# Addon-mapleCUx_Raspi-3V3-UART-CC2530-V04.net
KiCad netlist of a schematic drawn in EAGLE
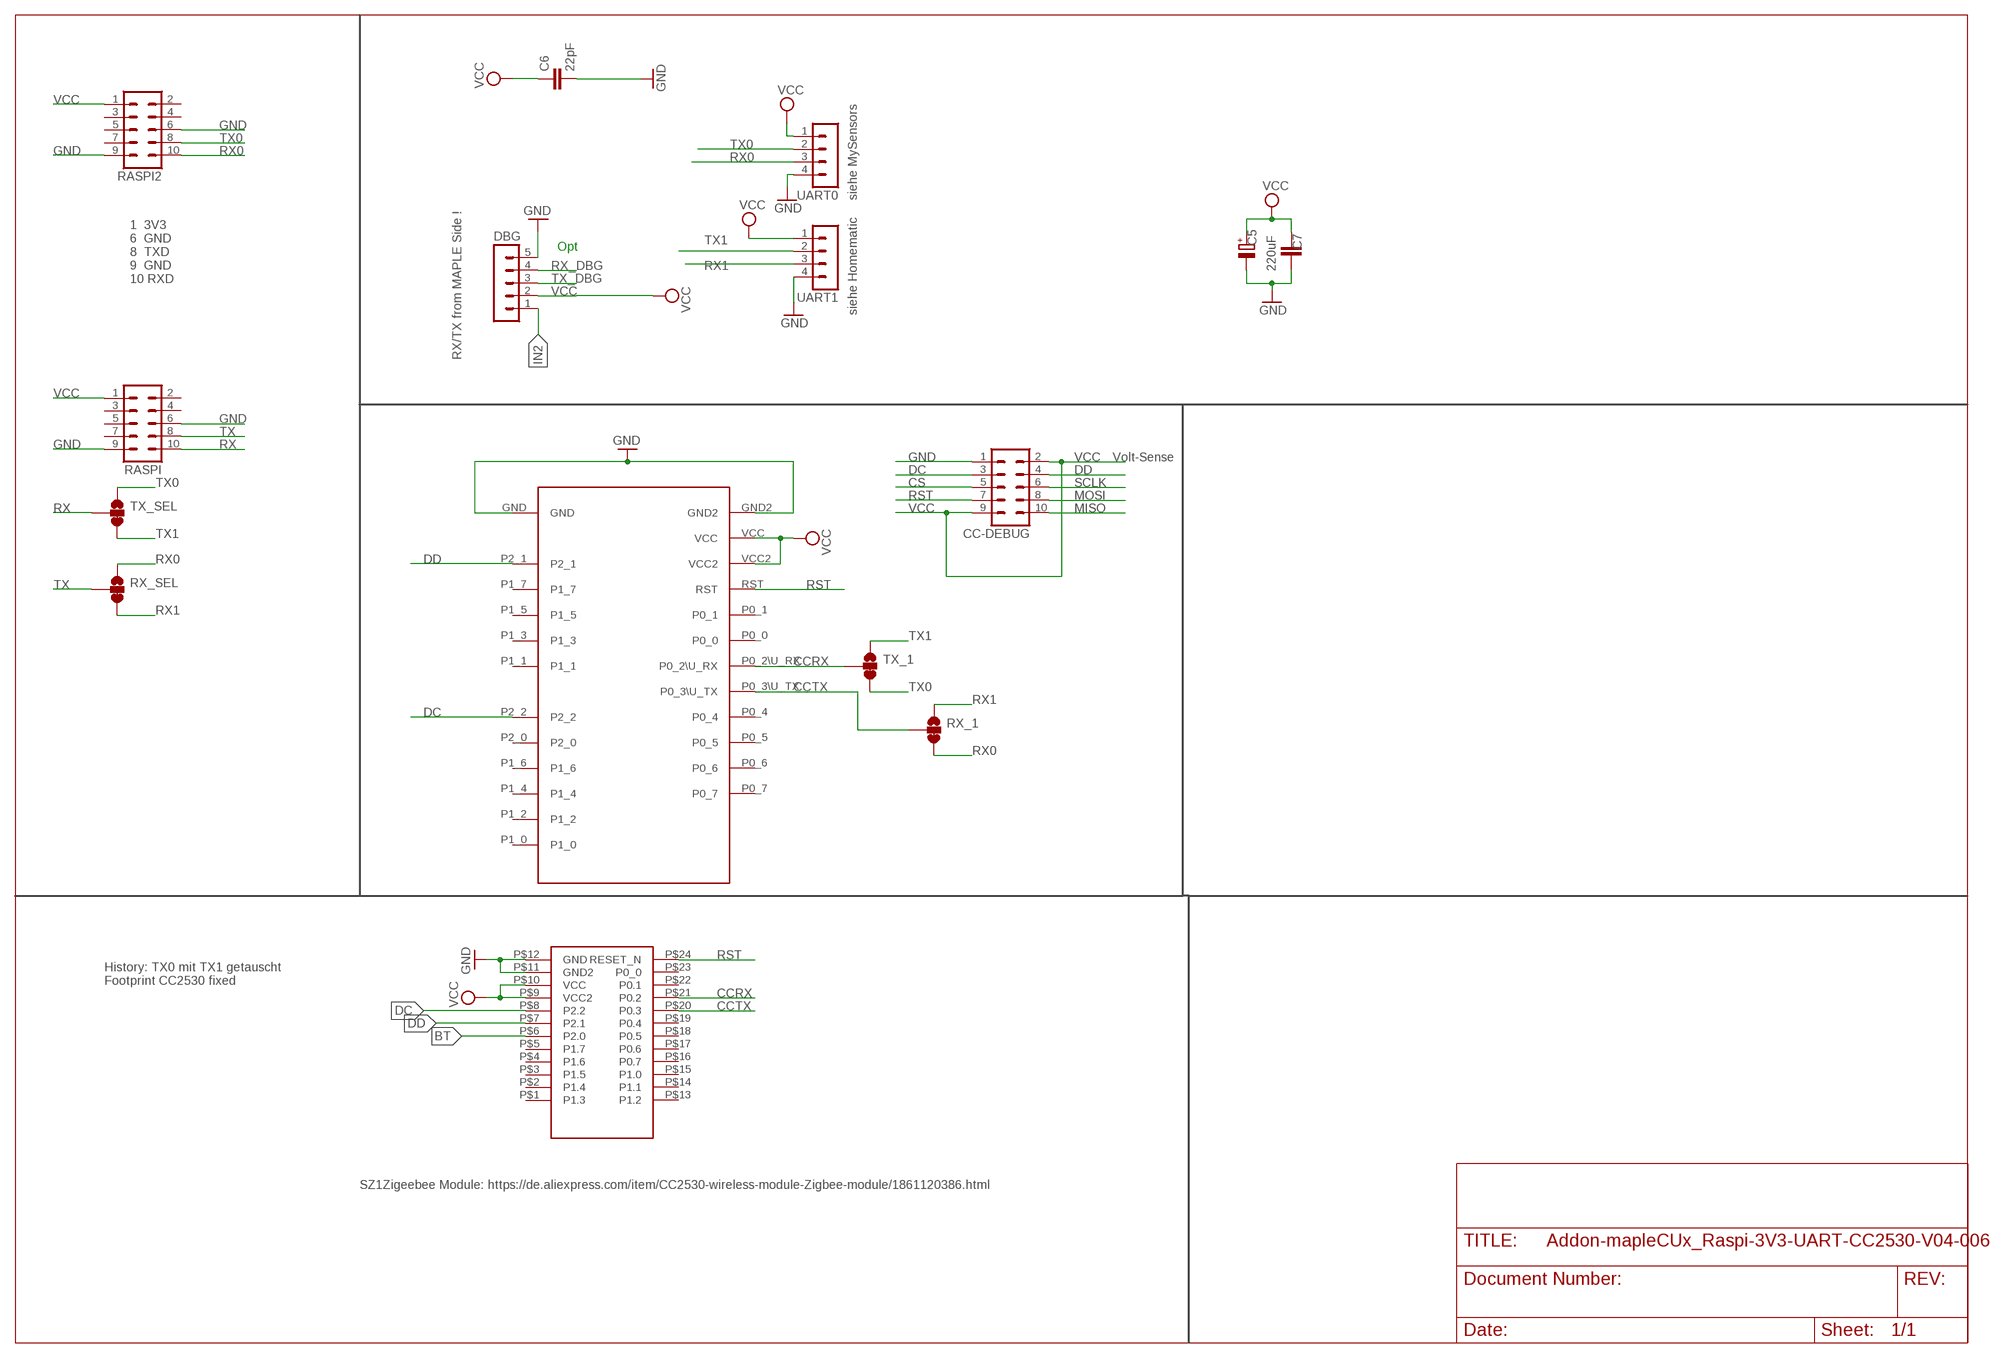
[diagram p0: schematic, sheet 1]

(export (version "E")
  (design (tool "Eeschema 10.0.6"))
  (components
    (comp (ref "C5")
      (value "220uF")
      (footprint "eagle-import:E5-8,5")
      (libsource (lib "eagle-import") (part "CPOL-EUE5-8.5"))
    )
    (comp (ref "C6")
      (value "22pF")
      (footprint "eagle-import:C0805")
      (libsource (lib "eagle-import") (part "C-EUC0805"))
    )
    (comp (ref "C7")
      (value "C-EUC1812")
      (footprint "eagle-import:C1812")
      (libsource (lib "eagle-import") (part "C-EUC1812"))
    )
    (comp (ref "CC-DEBUG")
      (value "MA05-2")
      (footprint "eagle-import:MA05-2")
      (libsource (lib "eagle-import") (part "MA05-2"))
    )
    (comp (ref "DBG")
      (value "MA05-1")
      (footprint "eagle-import:MA05-1")
      (libsource (lib "eagle-import") (part "MA05-1"))
    )
    (comp (ref "RASPI")
      (value "MA05-2")
      (footprint "eagle-import:MA05-2")
      (libsource (lib "eagle-import") (part "MA05-2"))
    )
    (comp (ref "RASPI2")
      (value "MA05-2")
      (footprint "eagle-import:MA05-2")
      (libsource (lib "eagle-import") (part "MA05-2"))
    )
    (comp (ref "RX_1")
      (value "JUMPER-SMT_3_1-NC_TRACE_SILK")
      (footprint "eagle-import:SMT-JUMPER_3_1-NC_TRACE_SILK")
      (libsource (lib "eagle-import") (part "JUMPER-SMT_3_1-NC_TRACE_SILK"))
    )
    (comp (ref "RX_SEL")
      (value "JUMPER-SMT_3_1-NC_TRACE_SILK")
      (footprint "eagle-import:SMT-JUMPER_3_1-NC_TRACE_SILK")
      (libsource (lib "eagle-import") (part "JUMPER-SMT_3_1-NC_TRACE_SILK"))
    )
    (comp (ref "TX_1")
      (value "JUMPER-SMT_3_1-NC_TRACE_SILK")
      (footprint "eagle-import:SMT-JUMPER_3_1-NC_TRACE_SILK")
      (libsource (lib "eagle-import") (part "JUMPER-SMT_3_1-NC_TRACE_SILK"))
    )
    (comp (ref "TX_SEL")
      (value "JUMPER-SMT_3_1-NC_TRACE_SILK")
      (footprint "eagle-import:SMT-JUMPER_3_1-NC_TRACE_SILK")
      (libsource (lib "eagle-import") (part "JUMPER-SMT_3_1-NC_TRACE_SILK"))
    )
    (comp (ref "U$1")
      (value "CC2530CC2530PA")
      (footprint "eagle-import:CC2530PA")
      (libsource (lib "eagle-import") (part "CC2530CC2530PA"))
    )
    (comp (ref "U$3")
      (value "CC2530_MODULE")
      (footprint "eagle-import:CC2530_DIL")
      (libsource (lib "eagle-import") (part "CC2530_MODULE"))
    )
    (comp (ref "UART0")
      (value "MA04-1")
      (footprint "eagle-import:MA04-1")
      (libsource (lib "eagle-import") (part "MA04-1"))
    )
    (comp (ref "UART1")
      (value "MA04-1")
      (footprint "eagle-import:MA04-1")
      (libsource (lib "eagle-import") (part "MA04-1"))
    )
  )
  (nets
    (net (code "1") (name "/CCRX") (class "Default")
      (node (ref "TX_1") (pin "2") (pinfunction "2_2") (pintype "passive"))
      (node (ref "U$1") (pin "P$21") (pinfunction "P0.2_P$21") (pintype "bidirectional"))
      (node (ref "U$3") (pin "P0_2\\U_RX") (pinfunction "P0_2\\U_RX_P0_2\\U_RX") (pintype "bidirectional"))
    )
    (net (code "2") (name "/CCTX") (class "Default")
      (node (ref "RX_1") (pin "2") (pinfunction "2_2") (pintype "passive"))
      (node (ref "U$1") (pin "P$20") (pinfunction "P0.3_P$20") (pintype "bidirectional"))
      (node (ref "U$3") (pin "P0_3\\U_TX") (pinfunction "P0_3\\U_TX_P0_3\\U_TX") (pintype "bidirectional"))
    )
    (net (code "3") (name "/CS") (class "Default")
      (node (ref "CC-DEBUG") (pin "5") (pinfunction "5_5") (pintype "passive"))
    )
    (net (code "4") (name "/MISO") (class "Default")
      (node (ref "CC-DEBUG") (pin "10") (pinfunction "10_10") (pintype "passive"))
    )
    (net (code "5") (name "/MOSI") (class "Default")
      (node (ref "CC-DEBUG") (pin "8") (pinfunction "8_8") (pintype "passive"))
    )
    (net (code "6") (name "/RST") (class "Default")
      (node (ref "CC-DEBUG") (pin "7") (pinfunction "7_7") (pintype "passive"))
      (node (ref "U$1") (pin "P$24") (pinfunction "RESET_N_P$24") (pintype "bidirectional"))
      (node (ref "U$3") (pin "RST") (pinfunction "RST_RST") (pintype "bidirectional"))
    )
    (net (code "7") (name "/RX") (class "Default")
      (node (ref "RASPI") (pin "10") (pinfunction "10_10") (pintype "passive"))
      (node (ref "TX_SEL") (pin "2") (pinfunction "2_2") (pintype "passive"))
    )
    (net (code "8") (name "/RX0") (class "Default")
      (node (ref "RASPI2") (pin "10") (pinfunction "10_10") (pintype "passive"))
      (node (ref "RX_1") (pin "3") (pinfunction "3_3") (pintype "passive"))
      (node (ref "RX_SEL") (pin "1") (pinfunction "1_1") (pintype "passive"))
      (node (ref "UART0") (pin "3") (pinfunction "3_3") (pintype "passive"))
    )
    (net (code "9") (name "/RX1") (class "Default")
      (node (ref "RX_1") (pin "1") (pinfunction "1_1") (pintype "passive"))
      (node (ref "RX_SEL") (pin "3") (pinfunction "3_3") (pintype "passive"))
      (node (ref "UART1") (pin "3") (pinfunction "3_3") (pintype "passive"))
    )
    (net (code "10") (name "/RX_DBG") (class "Default")
      (node (ref "DBG") (pin "4") (pinfunction "4_4") (pintype "passive"))
    )
    (net (code "11") (name "/SCLK") (class "Default")
      (node (ref "CC-DEBUG") (pin "6") (pinfunction "6_6") (pintype "passive"))
    )
    (net (code "12") (name "/TX") (class "Default")
      (node (ref "RASPI") (pin "8") (pinfunction "8_8") (pintype "passive"))
      (node (ref "RX_SEL") (pin "2") (pinfunction "2_2") (pintype "passive"))
    )
    (net (code "13") (name "/TX0") (class "Default")
      (node (ref "RASPI2") (pin "8") (pinfunction "8_8") (pintype "passive"))
      (node (ref "TX_1") (pin "3") (pinfunction "3_3") (pintype "passive"))
      (node (ref "TX_SEL") (pin "1") (pinfunction "1_1") (pintype "passive"))
      (node (ref "UART0") (pin "2") (pinfunction "2_2") (pintype "passive"))
    )
    (net (code "14") (name "/TX1") (class "Default")
      (node (ref "TX_1") (pin "1") (pinfunction "1_1") (pintype "passive"))
      (node (ref "TX_SEL") (pin "3") (pinfunction "3_3") (pintype "passive"))
      (node (ref "UART1") (pin "2") (pinfunction "2_2") (pintype "passive"))
    )
    (net (code "15") (name "/TX_DBG") (class "Default")
      (node (ref "DBG") (pin "3") (pinfunction "3_3") (pintype "passive"))
    )
    (net (code "16") (name "BT") (class "Default")
      (node (ref "U$1") (pin "P$6") (pinfunction "P2.0_P$6") (pintype "bidirectional"))
    )
    (net (code "17") (name "DC") (class "Default")
      (node (ref "CC-DEBUG") (pin "3") (pinfunction "3_3") (pintype "passive"))
      (node (ref "U$1") (pin "P$8") (pinfunction "P2.2_P$8") (pintype "bidirectional"))
      (node (ref "U$3") (pin "P2_2") (pinfunction "P2_2_P2_2") (pintype "bidirectional"))
    )
    (net (code "18") (name "DD") (class "Default")
      (node (ref "CC-DEBUG") (pin "4") (pinfunction "4_4") (pintype "passive"))
      (node (ref "U$1") (pin "P$7") (pinfunction "P2.1_P$7") (pintype "bidirectional"))
      (node (ref "U$3") (pin "P2_1") (pinfunction "P2_1_P2_1") (pintype "bidirectional"))
    )
    (net (code "19") (name "GND") (class "Default")
      (node (ref "C5") (pin "-") (pinfunction "-_-") (pintype "passive"))
      (node (ref "C6") (pin "2") (pinfunction "2_2") (pintype "passive"))
      (node (ref "C7") (pin "1") (pinfunction "1_1") (pintype "passive"))
      (node (ref "CC-DEBUG") (pin "1") (pinfunction "1_1") (pintype "passive"))
      (node (ref "DBG") (pin "5") (pinfunction "5_5") (pintype "passive"))
      (node (ref "RASPI") (pin "6") (pinfunction "6_6") (pintype "passive"))
      (node (ref "RASPI") (pin "9") (pinfunction "9_9") (pintype "passive"))
      (node (ref "RASPI2") (pin "6") (pinfunction "6_6") (pintype "passive"))
      (node (ref "RASPI2") (pin "9") (pinfunction "9_9") (pintype "passive"))
      (node (ref "U$1") (pin "P$11") (pinfunction "GND2_P$11") (pintype "bidirectional"))
      (node (ref "U$1") (pin "P$12") (pinfunction "GND_P$12") (pintype "bidirectional"))
      (node (ref "U$3") (pin "GND") (pinfunction "GND_GND") (pintype "bidirectional"))
      (node (ref "U$3") (pin "GND2") (pinfunction "GND2_GND2") (pintype "bidirectional"))
      (node (ref "UART0") (pin "4") (pinfunction "4_4") (pintype "passive"))
      (node (ref "UART1") (pin "4") (pinfunction "4_4") (pintype "passive"))
    )
    (net (code "20") (name "IN2") (class "Default")
      (node (ref "DBG") (pin "1") (pinfunction "1_1") (pintype "passive"))
    )
    (net (code "21") (name "VCC") (class "Default")
      (node (ref "C5") (pin "+") (pinfunction "+_+") (pintype "passive"))
      (node (ref "C6") (pin "1") (pinfunction "1_1") (pintype "passive"))
      (node (ref "C7") (pin "2") (pinfunction "2_2") (pintype "passive"))
      (node (ref "CC-DEBUG") (pin "2") (pinfunction "2_2") (pintype "passive"))
      (node (ref "CC-DEBUG") (pin "9") (pinfunction "9_9") (pintype "passive"))
      (node (ref "DBG") (pin "2") (pinfunction "2_2") (pintype "passive"))
      (node (ref "RASPI") (pin "1") (pinfunction "1_1") (pintype "passive"))
      (node (ref "RASPI2") (pin "1") (pinfunction "1_1") (pintype "passive"))
      (node (ref "U$1") (pin "P$10") (pinfunction "VCC_P$10") (pintype "bidirectional"))
      (node (ref "U$1") (pin "P$9") (pinfunction "VCC2_P$9") (pintype "bidirectional"))
      (node (ref "U$3") (pin "VCC") (pinfunction "VCC_VCC") (pintype "bidirectional"))
      (node (ref "U$3") (pin "VCC2") (pinfunction "VCC2_VCC2") (pintype "bidirectional"))
      (node (ref "UART0") (pin "1") (pinfunction "1_1") (pintype "passive"))
      (node (ref "UART1") (pin "1") (pinfunction "1_1") (pintype "passive"))
    )
    (net (code "22") (name "unconnected-(RASPI-Pad2)") (class "Default")
      (node (ref "RASPI") (pin "2") (pinfunction "2_2") (pintype "passive"))
    )
    (net (code "23") (name "unconnected-(RASPI-Pad3)") (class "Default")
      (node (ref "RASPI") (pin "3") (pinfunction "3_3") (pintype "passive"))
    )
    (net (code "24") (name "unconnected-(RASPI-Pad4)") (class "Default")
      (node (ref "RASPI") (pin "4") (pinfunction "4_4") (pintype "passive"))
    )
    (net (code "25") (name "unconnected-(RASPI-Pad5)") (class "Default")
      (node (ref "RASPI") (pin "5") (pinfunction "5_5") (pintype "passive"))
    )
    (net (code "26") (name "unconnected-(RASPI-Pad7)") (class "Default")
      (node (ref "RASPI") (pin "7") (pinfunction "7_7") (pintype "passive"))
    )
    (net (code "27") (name "unconnected-(RASPI2-Pad2)") (class "Default")
      (node (ref "RASPI2") (pin "2") (pinfunction "2_2") (pintype "passive"))
    )
    (net (code "28") (name "unconnected-(RASPI2-Pad3)") (class "Default")
      (node (ref "RASPI2") (pin "3") (pinfunction "3_3") (pintype "passive"))
    )
    (net (code "29") (name "unconnected-(RASPI2-Pad4)") (class "Default")
      (node (ref "RASPI2") (pin "4") (pinfunction "4_4") (pintype "passive"))
    )
    (net (code "30") (name "unconnected-(RASPI2-Pad5)") (class "Default")
      (node (ref "RASPI2") (pin "5") (pinfunction "5_5") (pintype "passive"))
    )
    (net (code "31") (name "unconnected-(RASPI2-Pad7)") (class "Default")
      (node (ref "RASPI2") (pin "7") (pinfunction "7_7") (pintype "passive"))
    )
    (net (code "32") (name "unconnected-(U$1-P0.1-PadP$22)") (class "Default")
      (node (ref "U$1") (pin "P$22") (pinfunction "P0.1_P$22") (pintype "bidirectional"))
    )
    (net (code "33") (name "unconnected-(U$1-P0.4-PadP$19)") (class "Default")
      (node (ref "U$1") (pin "P$19") (pinfunction "P0.4_P$19") (pintype "bidirectional"))
    )
    (net (code "34") (name "unconnected-(U$1-P0.5-PadP$18)") (class "Default")
      (node (ref "U$1") (pin "P$18") (pinfunction "P0.5_P$18") (pintype "bidirectional"))
    )
    (net (code "35") (name "unconnected-(U$1-P0.6-PadP$17)") (class "Default")
      (node (ref "U$1") (pin "P$17") (pinfunction "P0.6_P$17") (pintype "bidirectional"))
    )
    (net (code "36") (name "unconnected-(U$1-P0.7-PadP$16)") (class "Default")
      (node (ref "U$1") (pin "P$16") (pinfunction "P0.7_P$16") (pintype "bidirectional"))
    )
    (net (code "37") (name "unconnected-(U$1-P0_0-PadP$23)") (class "Default")
      (node (ref "U$1") (pin "P$23") (pinfunction "P0_0_P$23") (pintype "bidirectional"))
    )
    (net (code "38") (name "unconnected-(U$1-P1.0-PadP$15)") (class "Default")
      (node (ref "U$1") (pin "P$15") (pinfunction "P1.0_P$15") (pintype "bidirectional"))
    )
    (net (code "39") (name "unconnected-(U$1-P1.1-PadP$14)") (class "Default")
      (node (ref "U$1") (pin "P$14") (pinfunction "P1.1_P$14") (pintype "bidirectional"))
    )
    (net (code "40") (name "unconnected-(U$1-P1.2-PadP$13)") (class "Default")
      (node (ref "U$1") (pin "P$13") (pinfunction "P1.2_P$13") (pintype "bidirectional"))
    )
    (net (code "41") (name "unconnected-(U$1-P1.3-PadP$1)") (class "Default")
      (node (ref "U$1") (pin "P$1") (pinfunction "P1.3_P$1") (pintype "bidirectional"))
    )
    (net (code "42") (name "unconnected-(U$1-P1.4-PadP$2)") (class "Default")
      (node (ref "U$1") (pin "P$2") (pinfunction "P1.4_P$2") (pintype "bidirectional"))
    )
    (net (code "43") (name "unconnected-(U$1-P1.5-PadP$3)") (class "Default")
      (node (ref "U$1") (pin "P$3") (pinfunction "P1.5_P$3") (pintype "bidirectional"))
    )
    (net (code "44") (name "unconnected-(U$1-P1.6-PadP$4)") (class "Default")
      (node (ref "U$1") (pin "P$4") (pinfunction "P1.6_P$4") (pintype "bidirectional"))
    )
    (net (code "45") (name "unconnected-(U$1-P1.7-PadP$5)") (class "Default")
      (node (ref "U$1") (pin "P$5") (pinfunction "P1.7_P$5") (pintype "bidirectional"))
    )
    (net (code "46") (name "unconnected-(U$3-PadP0_0)") (class "Default")
      (node (ref "U$3") (pin "P0_0") (pinfunction "P0_0_P0_0") (pintype "bidirectional"))
    )
    (net (code "47") (name "unconnected-(U$3-PadP0_1)") (class "Default")
      (node (ref "U$3") (pin "P0_1") (pinfunction "P0_1_P0_1") (pintype "bidirectional"))
    )
    (net (code "48") (name "unconnected-(U$3-PadP0_4)") (class "Default")
      (node (ref "U$3") (pin "P0_4") (pinfunction "P0_4_P0_4") (pintype "bidirectional"))
    )
    (net (code "49") (name "unconnected-(U$3-PadP0_5)") (class "Default")
      (node (ref "U$3") (pin "P0_5") (pinfunction "P0_5_P0_5") (pintype "bidirectional"))
    )
    (net (code "50") (name "unconnected-(U$3-PadP0_6)") (class "Default")
      (node (ref "U$3") (pin "P0_6") (pinfunction "P0_6_P0_6") (pintype "bidirectional"))
    )
    (net (code "51") (name "unconnected-(U$3-PadP0_7)") (class "Default")
      (node (ref "U$3") (pin "P0_7") (pinfunction "P0_7_P0_7") (pintype "bidirectional"))
    )
    (net (code "52") (name "unconnected-(U$3-PadP1_0)") (class "Default")
      (node (ref "U$3") (pin "P1_0") (pinfunction "P1_0_P1_0") (pintype "bidirectional"))
    )
    (net (code "53") (name "unconnected-(U$3-PadP1_1)") (class "Default")
      (node (ref "U$3") (pin "P1_1") (pinfunction "P1_1_P1_1") (pintype "bidirectional"))
    )
    (net (code "54") (name "unconnected-(U$3-PadP1_2)") (class "Default")
      (node (ref "U$3") (pin "P1_2") (pinfunction "P1_2_P1_2") (pintype "bidirectional"))
    )
    (net (code "55") (name "unconnected-(U$3-PadP1_3)") (class "Default")
      (node (ref "U$3") (pin "P1_3") (pinfunction "P1_3_P1_3") (pintype "bidirectional"))
    )
    (net (code "56") (name "unconnected-(U$3-PadP1_4)") (class "Default")
      (node (ref "U$3") (pin "P1_4") (pinfunction "P1_4_P1_4") (pintype "bidirectional"))
    )
    (net (code "57") (name "unconnected-(U$3-PadP1_5)") (class "Default")
      (node (ref "U$3") (pin "P1_5") (pinfunction "P1_5_P1_5") (pintype "bidirectional"))
    )
    (net (code "58") (name "unconnected-(U$3-PadP1_6)") (class "Default")
      (node (ref "U$3") (pin "P1_6") (pinfunction "P1_6_P1_6") (pintype "bidirectional"))
    )
    (net (code "59") (name "unconnected-(U$3-PadP1_7)") (class "Default")
      (node (ref "U$3") (pin "P1_7") (pinfunction "P1_7_P1_7") (pintype "bidirectional"))
    )
    (net (code "60") (name "unconnected-(U$3-PadP2_0)") (class "Default")
      (node (ref "U$3") (pin "P2_0") (pinfunction "P2_0_P2_0") (pintype "bidirectional"))
    )
  )
)
